# Rele.net
KiCad netlist of a schematic drawn in Altium Designer
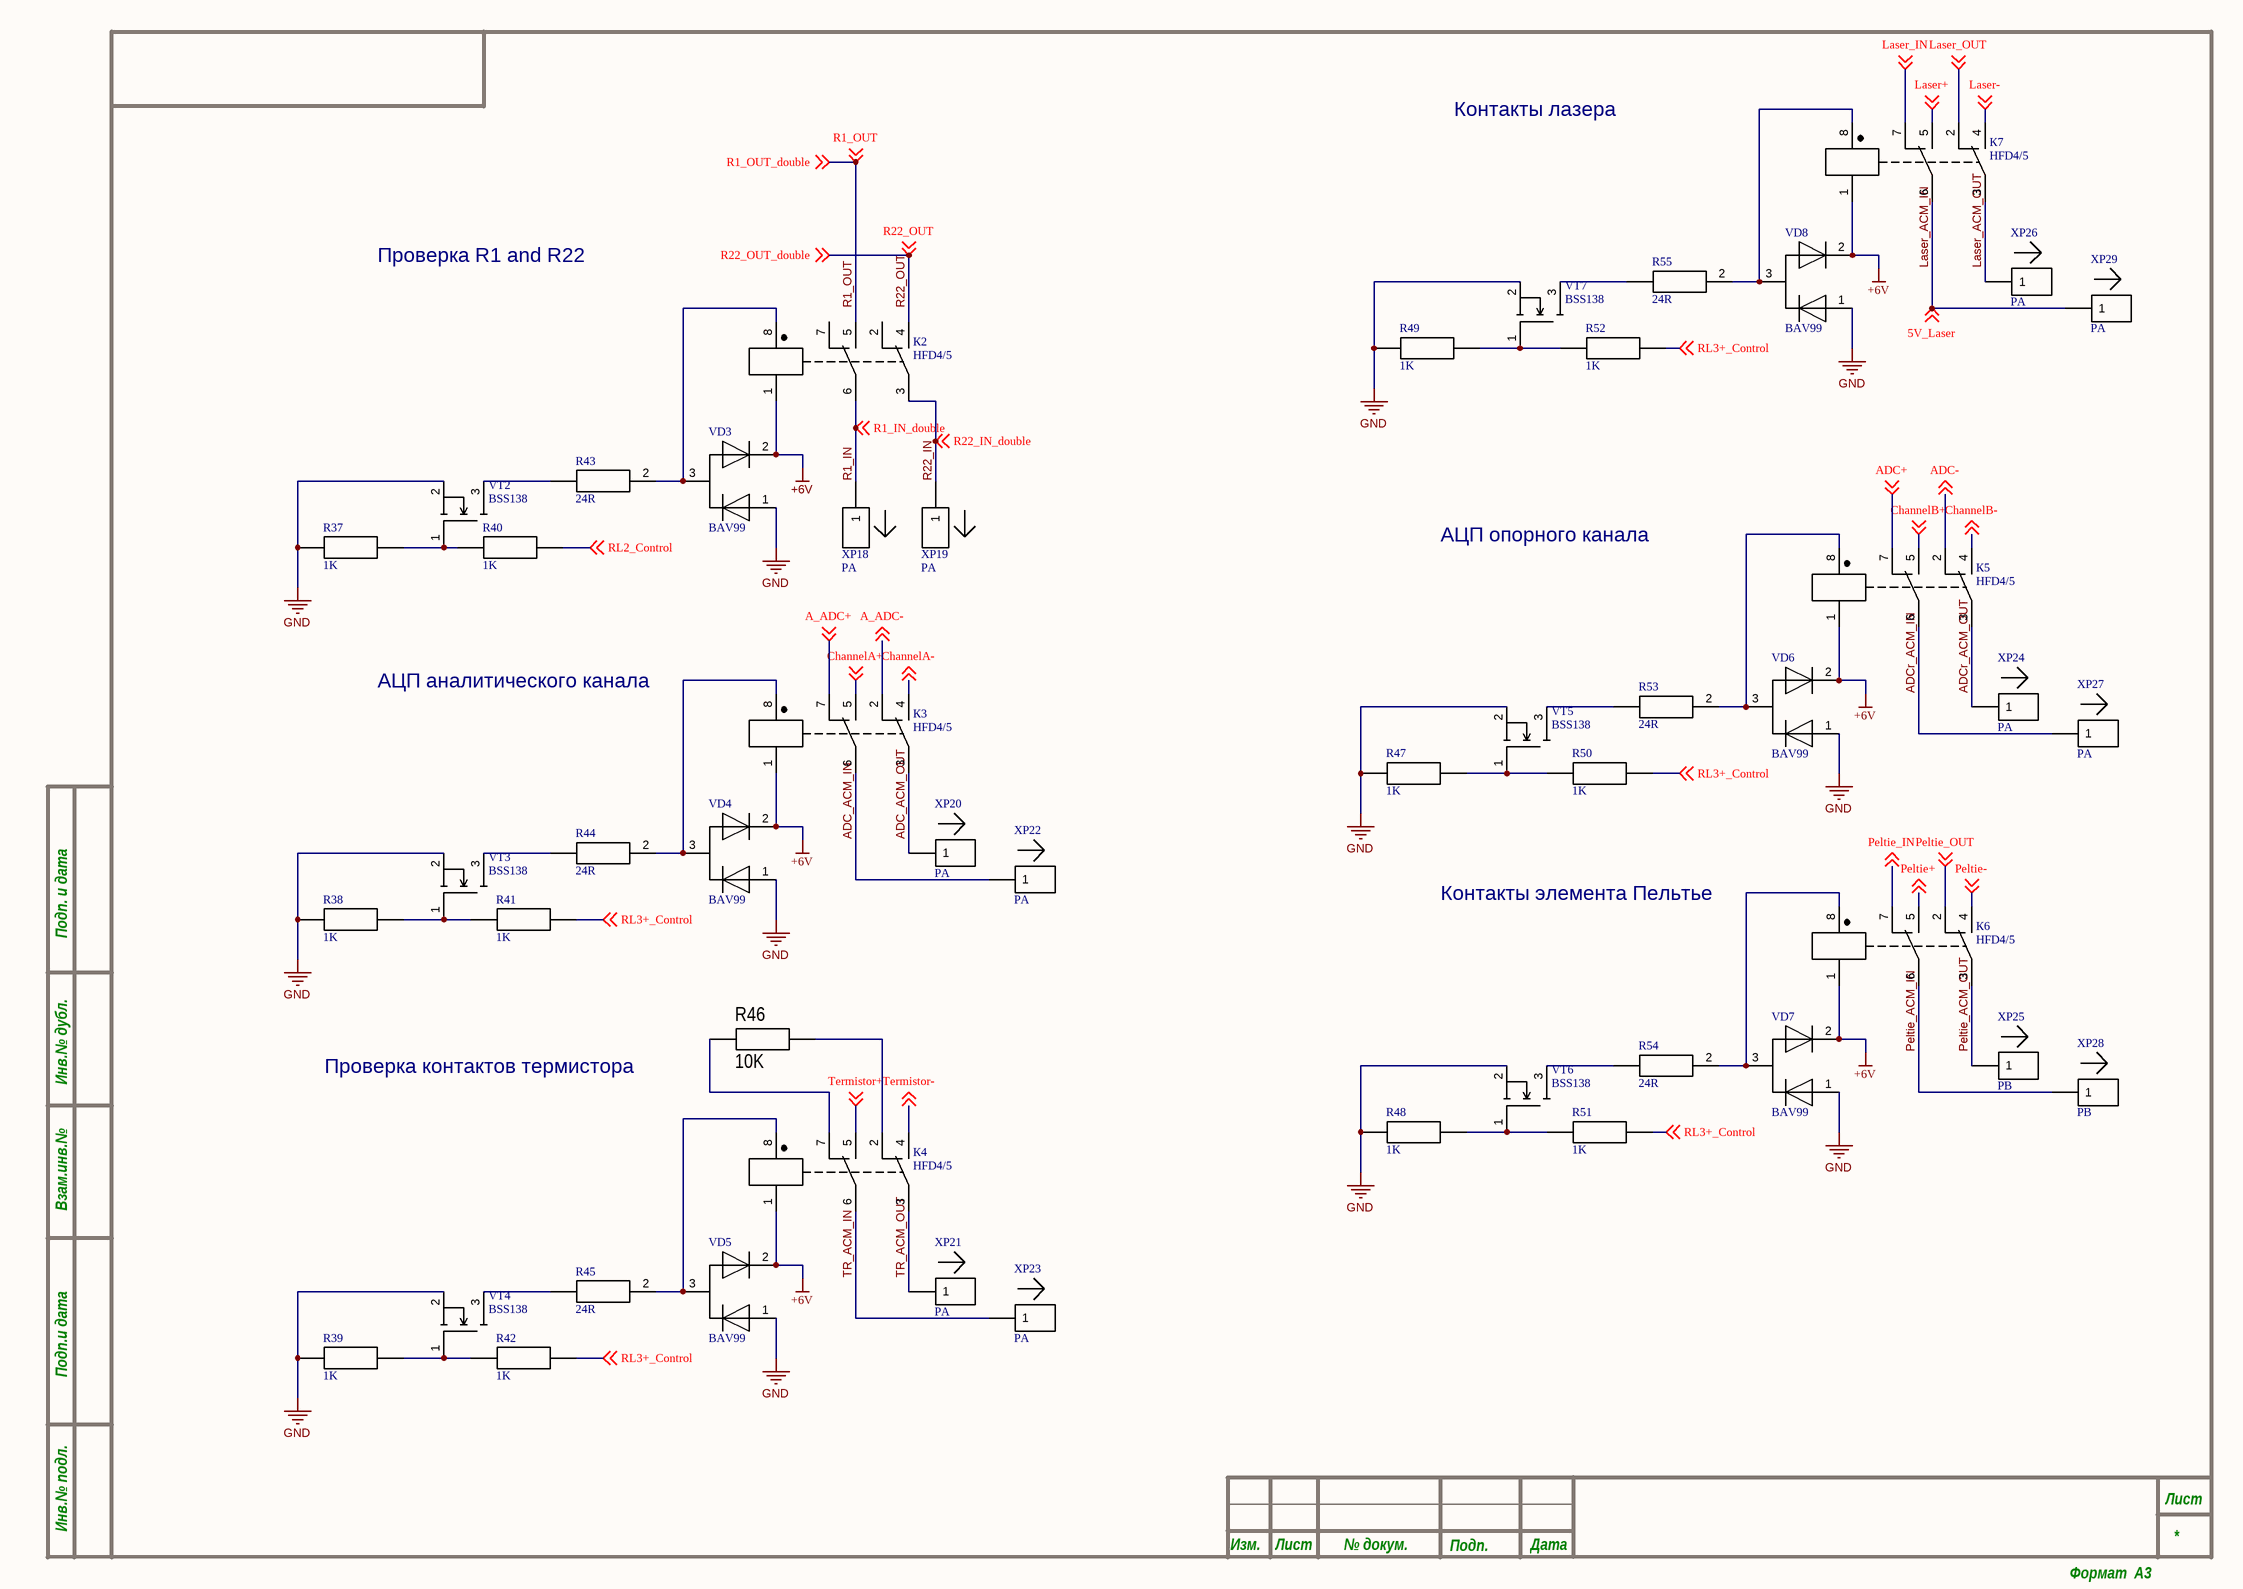
[diagram p0: Rele.SchDoc]

(export (version "E")
  (design (tool "Eeschema 10.0.6"))
  (components
    (comp (ref "R37")
      (value "1K")
      (footprint "R0402")
      (description "Resistor SMD 1K 1% 0402")
      (fields
        (field (name "PART NUMBER") "SMD RES 1 KOHM 1% ±100ppm/°C 0402")
        (field (name "ADDED_BY") "irdolgopolowa@yandex.ru")
      )
      (libsource (lib "Test_Stand_Pergam") (part "R0402-1K"))
    )
    (comp (ref "R38")
      (value "1K")
      (footprint "R0402")
      (description "Resistor SMD 1K 1% 0402")
      (fields
        (field (name "PART NUMBER") "SMD RES 1 KOHM 1% ±100ppm/°C 0402")
        (field (name "ADDED_BY") "irdolgopolowa@yandex.ru")
      )
      (libsource (lib "Test_Stand_Pergam") (part "R0402-1K"))
    )
    (comp (ref "R39")
      (value "1K")
      (footprint "R0402")
      (description "Resistor SMD 1K 1% 0402")
      (fields
        (field (name "PART NUMBER") "SMD RES 1 KOHM 1% ±100ppm/°C 0402")
        (field (name "ADDED_BY") "irdolgopolowa@yandex.ru")
      )
      (libsource (lib "Test_Stand_Pergam") (part "R0402-1K"))
    )
    (comp (ref "R40")
      (value "1K")
      (footprint "R0402")
      (description "Resistor SMD 1K 1% 0402")
      (fields
        (field (name "PART NUMBER") "SMD RES 1 KOHM 1% ±100ppm/°C 0402")
        (field (name "ADDED_BY") "irdolgopolowa@yandex.ru")
      )
      (libsource (lib "Test_Stand_Pergam") (part "R0402-1K"))
    )
    (comp (ref "R41")
      (value "1K")
      (footprint "R0402")
      (description "Resistor SMD 1K 1% 0402")
      (fields
        (field (name "PART NUMBER") "SMD RES 1 KOHM 1% ±100ppm/°C 0402")
        (field (name "ADDED_BY") "irdolgopolowa@yandex.ru")
      )
      (libsource (lib "Test_Stand_Pergam") (part "R0402-1K"))
    )
    (comp (ref "R42")
      (value "1K")
      (footprint "R0402")
      (description "Resistor SMD 1K 1% 0402")
      (fields
        (field (name "PART NUMBER") "SMD RES 1 KOHM 1% ±100ppm/°C 0402")
        (field (name "ADDED_BY") "irdolgopolowa@yandex.ru")
      )
      (libsource (lib "Test_Stand_Pergam") (part "R0402-1K"))
    )
    (comp (ref "R43")
      (value "24R")
      (footprint "R0402")
      (description "Resistor SMD 24R 1% 0402")
      (fields
        (field (name "PART NUMBER") "SMD RES 24R OHM 1% ±100ppm/°C 0402")
        (field (name "ADDED_BY") "Rutel@teslatec.ru")
      )
      (libsource (lib "Test_Stand_Pergam") (part "R0402-24R"))
    )
    (comp (ref "R44")
      (value "24R")
      (footprint "R0402")
      (description "Resistor SMD 24R 1% 0402")
      (fields
        (field (name "PART NUMBER") "SMD RES 24R OHM 1% ±100ppm/°C 0402")
        (field (name "ADDED_BY") "Rutel@teslatec.ru")
      )
      (libsource (lib "Test_Stand_Pergam") (part "R0402-24R"))
    )
    (comp (ref "R45")
      (value "24R")
      (footprint "R0402")
      (description "Resistor SMD 24R 1% 0402")
      (fields
        (field (name "PART NUMBER") "SMD RES 24R OHM 1% ±100ppm/°C 0402")
        (field (name "ADDED_BY") "Rutel@teslatec.ru")
      )
      (libsource (lib "Test_Stand_Pergam") (part "R0402-24R"))
    )
    (comp (ref "R46")
      (value "10K")
      (footprint "R0402")
      (description "Resistor SMD 10K 1% 0402")
      (fields
        (field (name "PART NUMBER") "SMD RES 10 KOHM 1% ±100ppm/°C 0402")
        (field (name "ADDED_BY") "Rutel@teslatec.ru")
      )
      (libsource (lib "Test_Stand_Pergam") (part "R0402-10K"))
    )
    (comp (ref "R47")
      (value "1K")
      (footprint "R0402")
      (description "Resistor SMD 1K 1% 0402")
      (fields
        (field (name "PART NUMBER") "SMD RES 1 KOHM 1% ±100ppm/°C 0402")
        (field (name "ADDED_BY") "irdolgopolowa@yandex.ru")
      )
      (libsource (lib "Test_Stand_Pergam") (part "R0402-1K"))
    )
    (comp (ref "R48")
      (value "1K")
      (footprint "R0402")
      (description "Resistor SMD 1K 1% 0402")
      (fields
        (field (name "PART NUMBER") "SMD RES 1 KOHM 1% ±100ppm/°C 0402")
        (field (name "ADDED_BY") "irdolgopolowa@yandex.ru")
      )
      (libsource (lib "Test_Stand_Pergam") (part "R0402-1K"))
    )
    (comp (ref "R49")
      (value "1K")
      (footprint "R0402")
      (description "Resistor SMD 1K 1% 0402")
      (fields
        (field (name "PART NUMBER") "SMD RES 1 KOHM 1% ±100ppm/°C 0402")
        (field (name "ADDED_BY") "irdolgopolowa@yandex.ru")
      )
      (libsource (lib "Test_Stand_Pergam") (part "R0402-1K"))
    )
    (comp (ref "R50")
      (value "1K")
      (footprint "R0402")
      (description "Resistor SMD 1K 1% 0402")
      (fields
        (field (name "PART NUMBER") "SMD RES 1 KOHM 1% ±100ppm/°C 0402")
        (field (name "ADDED_BY") "irdolgopolowa@yandex.ru")
      )
      (libsource (lib "Test_Stand_Pergam") (part "R0402-1K"))
    )
    (comp (ref "R51")
      (value "1K")
      (footprint "R0402")
      (description "Resistor SMD 1K 1% 0402")
      (fields
        (field (name "PART NUMBER") "SMD RES 1 KOHM 1% ±100ppm/°C 0402")
        (field (name "ADDED_BY") "irdolgopolowa@yandex.ru")
      )
      (libsource (lib "Test_Stand_Pergam") (part "R0402-1K"))
    )
    (comp (ref "R52")
      (value "1K")
      (footprint "R0402")
      (description "Resistor SMD 1K 1% 0402")
      (fields
        (field (name "PART NUMBER") "SMD RES 1 KOHM 1% ±100ppm/°C 0402")
        (field (name "ADDED_BY") "irdolgopolowa@yandex.ru")
      )
      (libsource (lib "Test_Stand_Pergam") (part "R0402-1K"))
    )
    (comp (ref "R53")
      (value "24R")
      (footprint "R0402")
      (description "Resistor SMD 24R 1% 0402")
      (fields
        (field (name "PART NUMBER") "SMD RES 24R OHM 1% ±100ppm/°C 0402")
        (field (name "ADDED_BY") "Rutel@teslatec.ru")
      )
      (libsource (lib "Test_Stand_Pergam") (part "R0402-24R"))
    )
    (comp (ref "R54")
      (value "24R")
      (footprint "R0402")
      (description "Resistor SMD 24R 1% 0402")
      (fields
        (field (name "PART NUMBER") "SMD RES 24R OHM 1% ±100ppm/°C 0402")
        (field (name "ADDED_BY") "Rutel@teslatec.ru")
      )
      (libsource (lib "Test_Stand_Pergam") (part "R0402-24R"))
    )
    (comp (ref "R55")
      (value "24R")
      (footprint "R0402")
      (description "Resistor SMD 24R 1% 0402")
      (fields
        (field (name "PART NUMBER") "SMD RES 24R OHM 1% ±100ppm/°C 0402")
        (field (name "ADDED_BY") "Rutel@teslatec.ru")
      )
      (libsource (lib "Test_Stand_Pergam") (part "R0402-24R"))
    )
    (comp (ref "VD3")
      (value "BAV99")
      (footprint "SOT-23-3")
      (description "BAV99, UMW, 70В, 200мА")
      (fields (field (name "ADDED_BY") "andrew@teslatec.ru"))
      (libsource (lib "Test_Stand_Pergam") (part "BAV99"))
    )
    (comp (ref "VD4")
      (value "BAV99")
      (footprint "SOT-23-3")
      (description "BAV99, UMW, 70В, 200мА")
      (fields (field (name "ADDED_BY") "andrew@teslatec.ru"))
      (libsource (lib "Test_Stand_Pergam") (part "BAV99"))
    )
    (comp (ref "VD5")
      (value "BAV99")
      (footprint "SOT-23-3")
      (description "BAV99, UMW, 70В, 200мА")
      (fields (field (name "ADDED_BY") "andrew@teslatec.ru"))
      (libsource (lib "Test_Stand_Pergam") (part "BAV99"))
    )
    (comp (ref "VD6")
      (value "BAV99")
      (footprint "SOT-23-3")
      (description "BAV99, UMW, 70В, 200мА")
      (fields (field (name "ADDED_BY") "andrew@teslatec.ru"))
      (libsource (lib "Test_Stand_Pergam") (part "BAV99"))
    )
    (comp (ref "VD7")
      (value "BAV99")
      (footprint "SOT-23-3")
      (description "BAV99, UMW, 70В, 200мА")
      (fields (field (name "ADDED_BY") "andrew@teslatec.ru"))
      (libsource (lib "Test_Stand_Pergam") (part "BAV99"))
    )
    (comp (ref "VD8")
      (value "BAV99")
      (footprint "SOT-23-3")
      (description "BAV99, UMW, 70В, 200мА")
      (fields (field (name "ADDED_BY") "andrew@teslatec.ru"))
      (libsource (lib "Test_Stand_Pergam") (part "BAV99"))
    )
    (comp (ref "VT2")
      (value "BSS138")
      (footprint "SOT-23-3")
      (description "N-Channel Logic Level Enhancement Mode Field Effect Transistor")
      (fields (field (name "ADDED_BY") "ma_lubushkin@teslatec.ru"))
      (libsource (lib "Test_Stand_Pergam") (part "BSS138"))
    )
    (comp (ref "VT3")
      (value "BSS138")
      (footprint "SOT-23-3")
      (description "N-Channel Logic Level Enhancement Mode Field Effect Transistor")
      (fields (field (name "ADDED_BY") "ma_lubushkin@teslatec.ru"))
      (libsource (lib "Test_Stand_Pergam") (part "BSS138"))
    )
    (comp (ref "VT4")
      (value "BSS138")
      (footprint "SOT-23-3")
      (description "N-Channel Logic Level Enhancement Mode Field Effect Transistor")
      (fields (field (name "ADDED_BY") "ma_lubushkin@teslatec.ru"))
      (libsource (lib "Test_Stand_Pergam") (part "BSS138"))
    )
    (comp (ref "VT5")
      (value "BSS138")
      (footprint "SOT-23-3")
      (description "N-Channel Logic Level Enhancement Mode Field Effect Transistor")
      (fields (field (name "ADDED_BY") "ma_lubushkin@teslatec.ru"))
      (libsource (lib "Test_Stand_Pergam") (part "BSS138"))
    )
    (comp (ref "VT6")
      (value "BSS138")
      (footprint "SOT-23-3")
      (description "N-Channel Logic Level Enhancement Mode Field Effect Transistor")
      (fields (field (name "ADDED_BY") "ma_lubushkin@teslatec.ru"))
      (libsource (lib "Test_Stand_Pergam") (part "BSS138"))
    )
    (comp (ref "VT7")
      (value "BSS138")
      (footprint "SOT-23-3")
      (description "N-Channel Logic Level Enhancement Mode Field Effect Transistor")
      (fields (field (name "ADDED_BY") "ma_lubushkin@teslatec.ru"))
      (libsource (lib "Test_Stand_Pergam") (part "BSS138"))
    )
    (comp (ref "XP18")
      (value "PA")
      (footprint "POGO PIN P100-A2/B1")
      (description "Pogo pin, 33.35x1.36")
      (fields
        (field (name "PART NUMBER") "P100-A2 / P100-A")
        (field (name "ADDED_BY") "irdolgopolowa@yandex.ru")
      )
      (libsource (lib "Test_Stand_Pergam") (part "P100-A2 / P100-A"))
    )
    (comp (ref "XP19")
      (value "PA")
      (footprint "POGO PIN P100-A2/B1")
      (description "Pogo pin, 33.35x1.36")
      (fields
        (field (name "PART NUMBER") "P100-A2 / P100-A")
        (field (name "ADDED_BY") "irdolgopolowa@yandex.ru")
      )
      (libsource (lib "Test_Stand_Pergam") (part "P100-A2 / P100-A"))
    )
    (comp (ref "XP20")
      (value "PA")
      (footprint "POGO PIN P100-A2/B1")
      (description "Pogo pin, 33.35x1.36")
      (fields
        (field (name "PART NUMBER") "P100-A2 / P100-A")
        (field (name "ADDED_BY") "irdolgopolowa@yandex.ru")
      )
      (libsource (lib "Test_Stand_Pergam") (part "P100-A2 / P100-A"))
    )
    (comp (ref "XP21")
      (value "PA")
      (footprint "POGO PIN P100-A2/B1")
      (description "Pogo pin, 33.35x1.36")
      (fields
        (field (name "PART NUMBER") "P100-A2 / P100-A")
        (field (name "ADDED_BY") "irdolgopolowa@yandex.ru")
      )
      (libsource (lib "Test_Stand_Pergam") (part "P100-A2 / P100-A"))
    )
    (comp (ref "XP22")
      (value "PA")
      (footprint "POGO PIN P100-A2/B1")
      (description "Pogo pin, 33.35x1.36")
      (fields
        (field (name "PART NUMBER") "P100-A2 / P100-A")
        (field (name "ADDED_BY") "irdolgopolowa@yandex.ru")
      )
      (libsource (lib "Test_Stand_Pergam") (part "P100-A2 / P100-A"))
    )
    (comp (ref "XP23")
      (value "PA")
      (footprint "POGO PIN P100-A2/B1")
      (description "Pogo pin, 33.35x1.36")
      (fields
        (field (name "PART NUMBER") "P100-A2 / P100-A")
        (field (name "ADDED_BY") "irdolgopolowa@yandex.ru")
      )
      (libsource (lib "Test_Stand_Pergam") (part "P100-A2 / P100-A"))
    )
    (comp (ref "XP24")
      (value "PA")
      (footprint "POGO PIN P100-A2/B1")
      (description "Pogo pin, 33.35x1.36")
      (fields
        (field (name "PART NUMBER") "P100-A2 / P100-A")
        (field (name "ADDED_BY") "irdolgopolowa@yandex.ru")
      )
      (libsource (lib "Test_Stand_Pergam") (part "P100-A2 / P100-A"))
    )
    (comp (ref "XP25")
      (value "PB")
      (footprint "POGO PIN P100-A2/B1")
      (description "Pogo pin, 33.35x1.36")
      (fields (field (name "PART NUMBER") "P100-B1") (field (name "ADDED_BY") "irdolgopolowa@yandex.ru"))
      (libsource (lib "Test_Stand_Pergam") (part "P100-B1"))
    )
    (comp (ref "XP26")
      (value "PA")
      (footprint "POGO PIN P100-A2/B1")
      (description "Pogo pin, 33.35x1.36")
      (fields
        (field (name "PART NUMBER") "P100-A2 / P100-A")
        (field (name "ADDED_BY") "irdolgopolowa@yandex.ru")
      )
      (libsource (lib "Test_Stand_Pergam") (part "P100-A2 / P100-A"))
    )
    (comp (ref "XP27")
      (value "PA")
      (footprint "POGO PIN P100-A2/B1")
      (description "Pogo pin, 33.35x1.36")
      (fields
        (field (name "PART NUMBER") "P100-A2 / P100-A")
        (field (name "ADDED_BY") "irdolgopolowa@yandex.ru")
      )
      (libsource (lib "Test_Stand_Pergam") (part "P100-A2 / P100-A"))
    )
    (comp (ref "XP28")
      (value "PB")
      (footprint "POGO PIN P100-A2/B1")
      (description "Pogo pin, 33.35x1.36")
      (fields (field (name "PART NUMBER") "P100-B1") (field (name "ADDED_BY") "irdolgopolowa@yandex.ru"))
      (libsource (lib "Test_Stand_Pergam") (part "P100-B1"))
    )
    (comp (ref "XP29")
      (value "PA")
      (footprint "POGO PIN P100-A2/B1")
      (description "Pogo pin, 33.35x1.36")
      (fields
        (field (name "PART NUMBER") "P100-A2 / P100-A")
        (field (name "ADDED_BY") "irdolgopolowa@yandex.ru")
      )
      (libsource (lib "Test_Stand_Pergam") (part "P100-A2 / P100-A"))
    )
    (comp (ref "К2")
      (value "HFD4/5")
      (footprint "DIP-8")
      (description "HFD4/5 (IM03TS) (1-1462037-8), 5VDC, 2A/250VAC DPDT")
      (fields (field (name "PART NUMBER") "HFD4/5SR") (field (name "ADDED_BY") "irdolgopolowa@yandex.ru"))
      (libsource (lib "Test_Stand_Pergam") (part "HFD4/5"))
    )
    (comp (ref "К3")
      (value "HFD4/5")
      (footprint "DIP-8")
      (description "HFD4/5 (IM03TS) (1-1462037-8), 5VDC, 2A/250VAC DPDT")
      (fields (field (name "PART NUMBER") "HFD4/5SR") (field (name "ADDED_BY") "irdolgopolowa@yandex.ru"))
      (libsource (lib "Test_Stand_Pergam") (part "HFD4/5"))
    )
    (comp (ref "К4")
      (value "HFD4/5")
      (footprint "DIP-8")
      (description "HFD4/5 (IM03TS) (1-1462037-8), 5VDC, 2A/250VAC DPDT")
      (fields (field (name "PART NUMBER") "HFD4/5SR") (field (name "ADDED_BY") "irdolgopolowa@yandex.ru"))
      (libsource (lib "Test_Stand_Pergam") (part "HFD4/5"))
    )
    (comp (ref "К5")
      (value "HFD4/5")
      (footprint "DIP-8")
      (description "HFD4/5 (IM03TS) (1-1462037-8), 5VDC, 2A/250VAC DPDT")
      (fields (field (name "PART NUMBER") "HFD4/5SR") (field (name "ADDED_BY") "irdolgopolowa@yandex.ru"))
      (libsource (lib "Test_Stand_Pergam") (part "HFD4/5"))
    )
    (comp (ref "К6")
      (value "HFD4/5")
      (footprint "DIP-8")
      (description "HFD4/5 (IM03TS) (1-1462037-8), 5VDC, 2A/250VAC DPDT")
      (fields (field (name "PART NUMBER") "HFD4/5SR") (field (name "ADDED_BY") "irdolgopolowa@yandex.ru"))
      (libsource (lib "Test_Stand_Pergam") (part "HFD4/5"))
    )
    (comp (ref "К7")
      (value "HFD4/5")
      (footprint "DIP-8")
      (description "HFD4/5 (IM03TS) (1-1462037-8), 5VDC, 2A/250VAC DPDT")
      (fields (field (name "PART NUMBER") "HFD4/5SR") (field (name "ADDED_BY") "irdolgopolowa@yandex.ru"))
      (libsource (lib "Test_Stand_Pergam") (part "HFD4/5"))
    )
  )
  (nets
    (net (code "1") (name "+6V") (class "Default")
      (node (ref "VD3") (pin "2") (pinfunction "2_2") (pintype "passive"))
      (node (ref "VD4") (pin "2") (pinfunction "2_2") (pintype "passive"))
      (node (ref "VD5") (pin "2") (pinfunction "2_2") (pintype "passive"))
      (node (ref "VD6") (pin "2") (pinfunction "2_2") (pintype "passive"))
      (node (ref "VD7") (pin "2") (pinfunction "2_2") (pintype "passive"))
      (node (ref "VD8") (pin "2") (pinfunction "2_2") (pintype "passive"))
      (node (ref "К2") (pin "1") (pinfunction "1_1") (pintype "passive"))
      (node (ref "К3") (pin "1") (pinfunction "1_1") (pintype "passive"))
      (node (ref "К4") (pin "1") (pinfunction "1_1") (pintype "passive"))
      (node (ref "К5") (pin "1") (pinfunction "1_1") (pintype "passive"))
      (node (ref "К6") (pin "1") (pinfunction "1_1") (pintype "passive"))
      (node (ref "К7") (pin "1") (pinfunction "1_1") (pintype "passive"))
    )
    (net (code "2") (name "/ADC_ACM_IN") (class "Default")
      (node (ref "XP22") (pin "1") (pinfunction "1_1") (pintype "passive"))
      (node (ref "К3") (pin "6") (pinfunction "6_6") (pintype "passive"))
    )
    (net (code "3") (name "/ADC_ACM_OUT") (class "Default")
      (node (ref "XP20") (pin "1") (pinfunction "1_1") (pintype "passive"))
      (node (ref "К3") (pin "3") (pinfunction "3_3") (pintype "passive"))
    )
    (net (code "4") (name "/ADCr_ACM_IN") (class "Default")
      (node (ref "XP27") (pin "1") (pinfunction "1_1") (pintype "passive"))
      (node (ref "К5") (pin "6") (pinfunction "6_6") (pintype "passive"))
    )
    (net (code "5") (name "/ADCr_ACM_OUT") (class "Default")
      (node (ref "XP24") (pin "1") (pinfunction "1_1") (pintype "passive"))
      (node (ref "К5") (pin "3") (pinfunction "3_3") (pintype "passive"))
    )
    (net (code "6") (name "/Laser_ACM_OUT") (class "Default")
      (node (ref "XP26") (pin "1") (pinfunction "1_1") (pintype "passive"))
      (node (ref "К7") (pin "3") (pinfunction "3_3") (pintype "passive"))
    )
    (net (code "7") (name "/Peltie_ACM_IN") (class "Default")
      (node (ref "XP28") (pin "1") (pinfunction "1_1") (pintype "passive"))
      (node (ref "К6") (pin "6") (pinfunction "6_6") (pintype "passive"))
    )
    (net (code "8") (name "/Peltie_ACM_OUT") (class "Default")
      (node (ref "XP25") (pin "1") (pinfunction "1_1") (pintype "passive"))
      (node (ref "К6") (pin "3") (pinfunction "3_3") (pintype "passive"))
    )
    (net (code "9") (name "/TR_ACM_IN") (class "Default")
      (node (ref "XP23") (pin "1") (pinfunction "1_1") (pintype "passive"))
      (node (ref "К4") (pin "6") (pinfunction "6_6") (pintype "passive"))
    )
    (net (code "10") (name "/TR_ACM_OUT") (class "Default")
      (node (ref "XP21") (pin "1") (pinfunction "1_1") (pintype "passive"))
      (node (ref "К4") (pin "3") (pinfunction "3_3") (pintype "passive"))
    )
    (net (code "11") (name "5V_Laser") (class "Default")
      (node (ref "XP29") (pin "1") (pinfunction "1_1") (pintype "passive"))
      (node (ref "К7") (pin "6") (pinfunction "6_6") (pintype "passive"))
    )
    (net (code "12") (name "ADC+") (class "Default")
      (node (ref "К5") (pin "7") (pinfunction "7_7") (pintype "passive"))
    )
    (net (code "13") (name "ADC-") (class "Default")
      (node (ref "К5") (pin "2") (pinfunction "2_2") (pintype "passive"))
    )
    (net (code "14") (name "A_ADC+") (class "Default")
      (node (ref "К3") (pin "7") (pinfunction "7_7") (pintype "passive"))
    )
    (net (code "15") (name "A_ADC-") (class "Default")
      (node (ref "К3") (pin "2") (pinfunction "2_2") (pintype "passive"))
    )
    (net (code "16") (name "ChannelA+") (class "Default")
      (node (ref "К3") (pin "5") (pinfunction "5_5") (pintype "passive"))
    )
    (net (code "17") (name "ChannelA-") (class "Default")
      (node (ref "К3") (pin "4") (pinfunction "4_4") (pintype "passive"))
    )
    (net (code "18") (name "ChannelB+") (class "Default")
      (node (ref "К5") (pin "5") (pinfunction "5_5") (pintype "passive"))
    )
    (net (code "19") (name "ChannelB-") (class "Default")
      (node (ref "К5") (pin "4") (pinfunction "4_4") (pintype "passive"))
    )
    (net (code "20") (name "GND") (class "Default")
      (node (ref "R37") (pin "1") (pinfunction "1_1") (pintype "passive"))
      (node (ref "R38") (pin "1") (pinfunction "1_1") (pintype "passive"))
      (node (ref "R39") (pin "1") (pinfunction "1_1") (pintype "passive"))
      (node (ref "R47") (pin "1") (pinfunction "1_1") (pintype "passive"))
      (node (ref "R48") (pin "1") (pinfunction "1_1") (pintype "passive"))
      (node (ref "R49") (pin "1") (pinfunction "1_1") (pintype "passive"))
      (node (ref "VD3") (pin "1") (pinfunction "1_1") (pintype "passive"))
      (node (ref "VD4") (pin "1") (pinfunction "1_1") (pintype "passive"))
      (node (ref "VD5") (pin "1") (pinfunction "1_1") (pintype "passive"))
      (node (ref "VD6") (pin "1") (pinfunction "1_1") (pintype "passive"))
      (node (ref "VD7") (pin "1") (pinfunction "1_1") (pintype "passive"))
      (node (ref "VD8") (pin "1") (pinfunction "1_1") (pintype "passive"))
      (node (ref "VT2") (pin "2") (pinfunction "2_2") (pintype "passive"))
      (node (ref "VT3") (pin "2") (pinfunction "2_2") (pintype "passive"))
      (node (ref "VT4") (pin "2") (pinfunction "2_2") (pintype "passive"))
      (node (ref "VT5") (pin "2") (pinfunction "2_2") (pintype "passive"))
      (node (ref "VT6") (pin "2") (pinfunction "2_2") (pintype "passive"))
      (node (ref "VT7") (pin "2") (pinfunction "2_2") (pintype "passive"))
    )
    (net (code "21") (name "Laser+") (class "Default")
      (node (ref "К7") (pin "5") (pinfunction "5_5") (pintype "passive"))
    )
    (net (code "22") (name "Laser-") (class "Default")
      (node (ref "К7") (pin "4") (pinfunction "4_4") (pintype "passive"))
    )
    (net (code "23") (name "Laser_IN") (class "Default")
      (node (ref "К7") (pin "7") (pinfunction "7_7") (pintype "passive"))
    )
    (net (code "24") (name "Laser_OUT") (class "Default")
      (node (ref "К7") (pin "2") (pinfunction "2_2") (pintype "passive"))
    )
    (net (code "25") (name "Net-(R37-Pad2)") (class "Default")
      (node (ref "R37") (pin "2") (pinfunction "2_2") (pintype "passive"))
      (node (ref "R40") (pin "1") (pinfunction "1_1") (pintype "passive"))
      (node (ref "VT2") (pin "1") (pinfunction "1_1") (pintype "passive"))
    )
    (net (code "26") (name "Net-(R38-Pad2)") (class "Default")
      (node (ref "R38") (pin "2") (pinfunction "2_2") (pintype "passive"))
      (node (ref "R41") (pin "1") (pinfunction "1_1") (pintype "passive"))
      (node (ref "VT3") (pin "1") (pinfunction "1_1") (pintype "passive"))
    )
    (net (code "27") (name "Net-(R39-Pad2)") (class "Default")
      (node (ref "R39") (pin "2") (pinfunction "2_2") (pintype "passive"))
      (node (ref "R42") (pin "1") (pinfunction "1_1") (pintype "passive"))
      (node (ref "VT4") (pin "1") (pinfunction "1_1") (pintype "passive"))
    )
    (net (code "28") (name "Net-(R43-Pad1)") (class "Default")
      (node (ref "R43") (pin "1") (pinfunction "1_1") (pintype "passive"))
      (node (ref "VT2") (pin "3") (pinfunction "3_3") (pintype "passive"))
    )
    (net (code "29") (name "Net-(R43-Pad2)") (class "Default")
      (node (ref "R43") (pin "2") (pinfunction "2_2") (pintype "passive"))
      (node (ref "VD3") (pin "3") (pinfunction "3_3") (pintype "passive"))
      (node (ref "К2") (pin "8") (pinfunction "8_8") (pintype "passive"))
    )
    (net (code "30") (name "Net-(R44-Pad1)") (class "Default")
      (node (ref "R44") (pin "1") (pinfunction "1_1") (pintype "passive"))
      (node (ref "VT3") (pin "3") (pinfunction "3_3") (pintype "passive"))
    )
    (net (code "31") (name "Net-(R44-Pad2)") (class "Default")
      (node (ref "R44") (pin "2") (pinfunction "2_2") (pintype "passive"))
      (node (ref "VD4") (pin "3") (pinfunction "3_3") (pintype "passive"))
      (node (ref "К3") (pin "8") (pinfunction "8_8") (pintype "passive"))
    )
    (net (code "32") (name "Net-(R45-Pad1)") (class "Default")
      (node (ref "R45") (pin "1") (pinfunction "1_1") (pintype "passive"))
      (node (ref "VT4") (pin "3") (pinfunction "3_3") (pintype "passive"))
    )
    (net (code "33") (name "Net-(R45-Pad2)") (class "Default")
      (node (ref "R45") (pin "2") (pinfunction "2_2") (pintype "passive"))
      (node (ref "VD5") (pin "3") (pinfunction "3_3") (pintype "passive"))
      (node (ref "К4") (pin "8") (pinfunction "8_8") (pintype "passive"))
    )
    (net (code "34") (name "Net-(R46-Pad1)") (class "Default")
      (node (ref "R46") (pin "1") (pinfunction "1_1") (pintype "passive"))
      (node (ref "К4") (pin "7") (pinfunction "7_7") (pintype "passive"))
    )
    (net (code "35") (name "Net-(R46-Pad2)") (class "Default")
      (node (ref "R46") (pin "2") (pinfunction "2_2") (pintype "passive"))
      (node (ref "К4") (pin "2") (pinfunction "2_2") (pintype "passive"))
    )
    (net (code "36") (name "Net-(R47-Pad2)") (class "Default")
      (node (ref "R47") (pin "2") (pinfunction "2_2") (pintype "passive"))
      (node (ref "R50") (pin "1") (pinfunction "1_1") (pintype "passive"))
      (node (ref "VT5") (pin "1") (pinfunction "1_1") (pintype "passive"))
    )
    (net (code "37") (name "Net-(R48-Pad2)") (class "Default")
      (node (ref "R48") (pin "2") (pinfunction "2_2") (pintype "passive"))
      (node (ref "R51") (pin "1") (pinfunction "1_1") (pintype "passive"))
      (node (ref "VT6") (pin "1") (pinfunction "1_1") (pintype "passive"))
    )
    (net (code "38") (name "Net-(R49-Pad2)") (class "Default")
      (node (ref "R49") (pin "2") (pinfunction "2_2") (pintype "passive"))
      (node (ref "R52") (pin "1") (pinfunction "1_1") (pintype "passive"))
      (node (ref "VT7") (pin "1") (pinfunction "1_1") (pintype "passive"))
    )
    (net (code "39") (name "Net-(R53-Pad1)") (class "Default")
      (node (ref "R53") (pin "1") (pinfunction "1_1") (pintype "passive"))
      (node (ref "VT5") (pin "3") (pinfunction "3_3") (pintype "passive"))
    )
    (net (code "40") (name "Net-(R53-Pad2)") (class "Default")
      (node (ref "R53") (pin "2") (pinfunction "2_2") (pintype "passive"))
      (node (ref "VD6") (pin "3") (pinfunction "3_3") (pintype "passive"))
      (node (ref "К5") (pin "8") (pinfunction "8_8") (pintype "passive"))
    )
    (net (code "41") (name "Net-(R54-Pad1)") (class "Default")
      (node (ref "R54") (pin "1") (pinfunction "1_1") (pintype "passive"))
      (node (ref "VT6") (pin "3") (pinfunction "3_3") (pintype "passive"))
    )
    (net (code "42") (name "Net-(R54-Pad2)") (class "Default")
      (node (ref "R54") (pin "2") (pinfunction "2_2") (pintype "passive"))
      (node (ref "VD7") (pin "3") (pinfunction "3_3") (pintype "passive"))
      (node (ref "К6") (pin "8") (pinfunction "8_8") (pintype "passive"))
    )
    (net (code "43") (name "Net-(R55-Pad1)") (class "Default")
      (node (ref "R55") (pin "1") (pinfunction "1_1") (pintype "passive"))
      (node (ref "VT7") (pin "3") (pinfunction "3_3") (pintype "passive"))
    )
    (net (code "44") (name "Net-(R55-Pad2)") (class "Default")
      (node (ref "R55") (pin "2") (pinfunction "2_2") (pintype "passive"))
      (node (ref "VD8") (pin "3") (pinfunction "3_3") (pintype "passive"))
      (node (ref "К7") (pin "8") (pinfunction "8_8") (pintype "passive"))
    )
    (net (code "45") (name "Peltie+") (class "Default")
      (node (ref "К6") (pin "5") (pinfunction "5_5") (pintype "passive"))
    )
    (net (code "46") (name "Peltie-") (class "Default")
      (node (ref "К6") (pin "4") (pinfunction "4_4") (pintype "passive"))
    )
    (net (code "47") (name "Peltie_IN") (class "Default")
      (node (ref "К6") (pin "7") (pinfunction "7_7") (pintype "passive"))
    )
    (net (code "48") (name "Peltie_OUT") (class "Default")
      (node (ref "К6") (pin "2") (pinfunction "2_2") (pintype "passive"))
    )
    (net (code "49") (name "R1_IN_double") (class "Default")
      (node (ref "XP18") (pin "1") (pinfunction "1_1") (pintype "passive"))
      (node (ref "К2") (pin "6") (pinfunction "6_6") (pintype "passive"))
    )
    (net (code "50") (name "R1_OUT") (class "Default")
      (node (ref "К2") (pin "5") (pinfunction "5_5") (pintype "passive"))
    )
    (net (code "51") (name "R22_IN_double") (class "Default")
      (node (ref "XP19") (pin "1") (pinfunction "1_1") (pintype "passive"))
      (node (ref "К2") (pin "3") (pinfunction "3_3") (pintype "passive"))
    )
    (net (code "52") (name "R22_OUT") (class "Default")
      (node (ref "К2") (pin "4") (pinfunction "4_4") (pintype "passive"))
    )
    (net (code "53") (name "RL2_Control") (class "Default")
      (node (ref "R40") (pin "2") (pinfunction "2_2") (pintype "passive"))
    )
    (net (code "54") (name "RL3+_Control") (class "Default")
      (node (ref "R41") (pin "2") (pinfunction "2_2") (pintype "passive"))
      (node (ref "R42") (pin "2") (pinfunction "2_2") (pintype "passive"))
      (node (ref "R50") (pin "2") (pinfunction "2_2") (pintype "passive"))
      (node (ref "R51") (pin "2") (pinfunction "2_2") (pintype "passive"))
      (node (ref "R52") (pin "2") (pinfunction "2_2") (pintype "passive"))
    )
    (net (code "55") (name "Termistor+") (class "Default")
      (node (ref "К4") (pin "5") (pinfunction "5_5") (pintype "passive"))
    )
    (net (code "56") (name "Termistor-") (class "Default")
      (node (ref "К4") (pin "4") (pinfunction "4_4") (pintype "passive"))
    )
    (net (code "57") (name "unconnected-(К2-Pad2)") (class "Default")
      (node (ref "К2") (pin "2") (pinfunction "2_2") (pintype "passive"))
    )
    (net (code "58") (name "unconnected-(К2-Pad7)") (class "Default")
      (node (ref "К2") (pin "7") (pinfunction "7_7") (pintype "passive"))
    )
  )
)
